# portableSpcPlayer.net
KiCad netlist of a schematic drawn in EAGLE
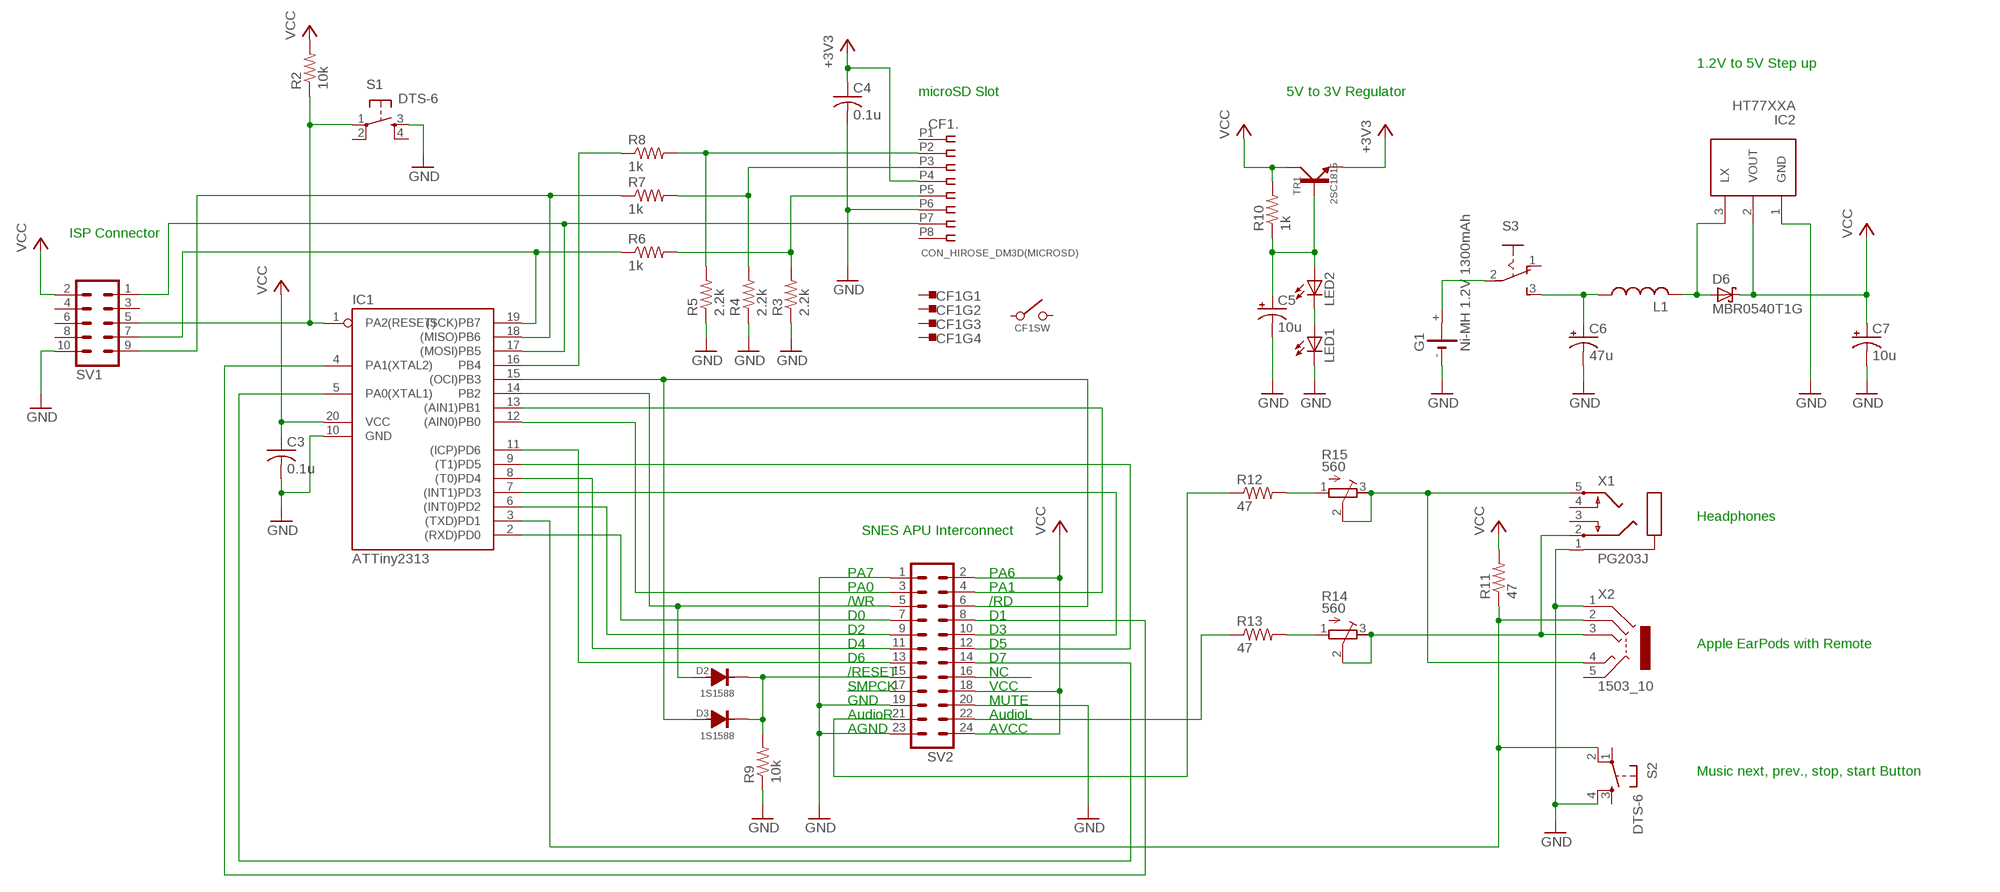
[diagram p0: schematic, sheet 1]

(export (version "E")
  (design (tool "Eeschema 10.0.6"))
  (components
    (comp (ref "C3")
      (value "0.1u")
      (footprint "eagle-import:C050-024X044")
      (libsource (lib "eagle-import") (part "C-US050-024X044"))
    )
    (comp (ref "C4")
      (value "0.1u")
      (footprint "eagle-import:C050-024X044")
      (libsource (lib "eagle-import") (part "C-US050-024X044"))
    )
    (comp (ref "C5")
      (value "10u")
      (footprint "eagle-import:E5-5")
      (libsource (lib "eagle-import") (part "CPOL-USE5-5"))
    )
    (comp (ref "C6")
      (value "47u")
      (footprint "eagle-import:E5-5")
      (libsource (lib "eagle-import") (part "CPOL-USE5-5"))
    )
    (comp (ref "C7")
      (value "10u")
      (footprint "eagle-import:E5-5")
      (libsource (lib "eagle-import") (part "CPOL-USE5-5"))
    )
    (comp (ref "CF1")
      (value "CON_HIROSE_DM3D(MICROSD)")
      (footprint "eagle-import:HIROSE_DM3D(MICRO-SD)")
      (libsource (lib "eagle-import") (part "CON_HIROSE_DM3D(MICROSD)"))
    )
    (comp (ref "D2")
      (value "1S1588")
      (footprint "eagle-import:DIODE-D-5")
      (libsource (lib "eagle-import") (part "1S1588"))
    )
    (comp (ref "D3")
      (value "1S1588")
      (footprint "eagle-import:DIODE-D-5")
      (libsource (lib "eagle-import") (part "1S1588"))
    )
    (comp (ref "D6")
      (value "MBR0540T1G")
      (footprint "eagle-import:DO41-7.6")
      (libsource (lib "eagle-import") (part "1N5817-B"))
    )
    (comp (ref "G1")
      (value "Ni-MH 1.2V 1300mAh")
      (footprint "eagle-import:CRAA")
      (libsource (lib "eagle-import") (part "CR-AA"))
    )
    (comp (ref "IC1")
      (value "ATTiny2313")
      (footprint "eagle-import:DIL20")
      (libsource (lib "eagle-import") (part "AT90S2313P"))
    )
    (comp (ref "IC2")
      (value "HT77XXA")
      (footprint "eagle-import:TO92-N")
      (libsource (lib "eagle-import") (part "HT77XXA"))
    )
    (comp (ref "L1")
      (value "L-US0204/7")
      (footprint "eagle-import:0204_7")
      (libsource (lib "eagle-import") (part "L-US0204/7"))
    )
    (comp (ref "LED1")
      (value "LED3MM")
      (footprint "eagle-import:LED3MM")
      (libsource (lib "eagle-import") (part "LED3MM"))
    )
    (comp (ref "LED2")
      (value "LED3MM")
      (footprint "eagle-import:LED3MM")
      (libsource (lib "eagle-import") (part "LED3MM"))
    )
    (comp (ref "R2")
      (value "10k")
      (footprint "eagle-import:0204_5")
      (libsource (lib "eagle-import") (part "R-US_0204/5"))
    )
    (comp (ref "R3")
      (value "2.2k")
      (footprint "eagle-import:0204_5")
      (libsource (lib "eagle-import") (part "R-US_0204/5"))
    )
    (comp (ref "R4")
      (value "2.2k")
      (footprint "eagle-import:0204_5")
      (libsource (lib "eagle-import") (part "R-US_0204/5"))
    )
    (comp (ref "R5")
      (value "2.2k")
      (footprint "eagle-import:0204_5")
      (libsource (lib "eagle-import") (part "R-US_0204/5"))
    )
    (comp (ref "R6")
      (value "1k")
      (footprint "eagle-import:0204_5")
      (libsource (lib "eagle-import") (part "R-US_0204/5"))
    )
    (comp (ref "R7")
      (value "1k")
      (footprint "eagle-import:0204_5")
      (libsource (lib "eagle-import") (part "R-US_0204/5"))
    )
    (comp (ref "R8")
      (value "1k")
      (footprint "eagle-import:0204_5")
      (libsource (lib "eagle-import") (part "R-US_0204/5"))
    )
    (comp (ref "R9")
      (value "10k")
      (footprint "eagle-import:0204_5")
      (libsource (lib "eagle-import") (part "R-US_0204/5"))
    )
    (comp (ref "R10")
      (value "1k")
      (footprint "eagle-import:0204_5")
      (libsource (lib "eagle-import") (part "R-US_0204/5"))
    )
    (comp (ref "R11")
      (value "47")
      (footprint "eagle-import:0204_5")
      (libsource (lib "eagle-import") (part "R-US_0204/5"))
    )
    (comp (ref "R12")
      (value "47")
      (footprint "eagle-import:0204_5")
      (libsource (lib "eagle-import") (part "R-US_0204/5"))
    )
    (comp (ref "R13")
      (value "47")
      (footprint "eagle-import:0204_5")
      (libsource (lib "eagle-import") (part "R-US_0204/5"))
    )
    (comp (ref "R14")
      (value "560")
      (footprint "eagle-import:RTRIM4G_J")
      (libsource (lib "eagle-import") (part "R-TRIMM4G/J"))
    )
    (comp (ref "R15")
      (value "560")
      (footprint "eagle-import:RTRIM4G_J")
      (libsource (lib "eagle-import") (part "R-TRIMM4G/J"))
    )
    (comp (ref "S1")
      (value "DTS-6")
      (footprint "eagle-import:DTS-6")
      (libsource (lib "eagle-import") (part "DTS-6"))
    )
    (comp (ref "S2")
      (value "DTS-6")
      (footprint "eagle-import:DTS-6")
      (libsource (lib "eagle-import") (part "DTS-6"))
    )
    (comp (ref "S3")
      (value "255SB")
      (footprint "eagle-import:255SB")
      (libsource (lib "eagle-import") (part "255SB"))
    )
    (comp (ref "SV1")
      (value "MA05-2")
      (footprint "eagle-import:MA05-2")
      (libsource (lib "eagle-import") (part "MA05-2"))
    )
    (comp (ref "SV2")
      (value "MA12-2")
      (footprint "eagle-import:MA12-2")
      (libsource (lib "eagle-import") (part "MA12-2"))
    )
    (comp (ref "TR1")
      (value "2SC1815")
      (footprint "eagle-import:TO92-")
      (libsource (lib "eagle-import") (part "2SC1815"))
    )
    (comp (ref "X1")
      (value "PG203J")
      (footprint "eagle-import:PG203J")
      (libsource (lib "eagle-import") (part "PG203J"))
    )
    (comp (ref "X2")
      (value "1503_10")
      (footprint "eagle-import:1503_10")
      (libsource (lib "eagle-import") (part "1503_10"))
    )
  )
  (nets
    (net (code "1") (name "+3V3") (class "Default")
      (node (ref "C4") (pin "1") (pinfunction "1_1") (pintype "passive"))
      (node (ref "CF1") (pin "P4") (pinfunction "4_P4") (pintype "passive"))
      (node (ref "TR1") (pin "3") (pinfunction "3_3") (pintype "passive"))
    )
    (net (code "2") (name "GND") (class "Default")
      (node (ref "C3") (pin "2") (pinfunction "2_2") (pintype "passive"))
      (node (ref "C4") (pin "2") (pinfunction "2_2") (pintype "passive"))
      (node (ref "C5") (pin "-") (pinfunction "-_-") (pintype "passive"))
      (node (ref "C6") (pin "-") (pinfunction "-_-") (pintype "passive"))
      (node (ref "C7") (pin "-") (pinfunction "-_-") (pintype "passive"))
      (node (ref "CF1") (pin "P6") (pinfunction "6_P6") (pintype "passive"))
      (node (ref "G1") (pin "-") (pinfunction "-_-") (pintype "passive"))
      (node (ref "IC1") (pin "10") (pinfunction "GND_10") (pintype "power_in"))
      (node (ref "IC2") (pin "1") (pinfunction "GND_1") (pintype "power_in"))
      (node (ref "LED1") (pin "K") (pinfunction "C_K") (pintype "passive"))
      (node (ref "R3") (pin "1") (pinfunction "1_1") (pintype "passive"))
      (node (ref "R4") (pin "1") (pinfunction "1_1") (pintype "passive"))
      (node (ref "R5") (pin "1") (pinfunction "1_1") (pintype "passive"))
      (node (ref "R9") (pin "1") (pinfunction "1_1") (pintype "passive"))
      (node (ref "S1") (pin "3") (pinfunction "3_3") (pintype "passive"))
      (node (ref "S2") (pin "4") (pinfunction "4_4") (pintype "passive"))
      (node (ref "SV1") (pin "10") (pinfunction "10_10") (pintype "passive"))
      (node (ref "SV2") (pin "1") (pinfunction "1_1") (pintype "passive"))
      (node (ref "SV2") (pin "19") (pinfunction "19_19") (pintype "passive"))
      (node (ref "SV2") (pin "20") (pinfunction "20_20") (pintype "passive"))
      (node (ref "SV2") (pin "23") (pinfunction "23_23") (pintype "passive"))
      (node (ref "X1") (pin "1") (pinfunction "1_1") (pintype "passive"))
      (node (ref "X2") (pin "1") (pinfunction "1_1") (pintype "passive"))
    )
    (net (code "3") (name "Net-(C5-Pad+)") (class "Default")
      (node (ref "C5") (pin "+") (pinfunction "+_+") (pintype "passive"))
      (node (ref "LED2") (pin "A") (pinfunction "A_A") (pintype "passive"))
      (node (ref "R10") (pin "1") (pinfunction "1_1") (pintype "passive"))
      (node (ref "TR1") (pin "1") (pinfunction "1_1") (pintype "passive"))
    )
    (net (code "4") (name "Net-(CF1A-2)") (class "Default")
      (node (ref "CF1") (pin "P2") (pinfunction "2_P2") (pintype "passive"))
      (node (ref "R5") (pin "2") (pinfunction "2_2") (pintype "passive"))
      (node (ref "R8") (pin "2") (pinfunction "2_2") (pintype "passive"))
    )
    (net (code "5") (name "Net-(CF1A-3)") (class "Default")
      (node (ref "CF1") (pin "P3") (pinfunction "3_P3") (pintype "passive"))
      (node (ref "R4") (pin "2") (pinfunction "2_2") (pintype "passive"))
      (node (ref "R7") (pin "2") (pinfunction "2_2") (pintype "passive"))
    )
    (net (code "6") (name "Net-(CF1A-5)") (class "Default")
      (node (ref "CF1") (pin "P5") (pinfunction "5_P5") (pintype "passive"))
      (node (ref "R3") (pin "2") (pinfunction "2_2") (pintype "passive"))
      (node (ref "R6") (pin "2") (pinfunction "2_2") (pintype "passive"))
    )
    (net (code "7") (name "Net-(CF1A-7)") (class "Default")
      (node (ref "CF1") (pin "P7") (pinfunction "7_P7") (pintype "passive"))
      (node (ref "IC1") (pin "17") (pinfunction "(MOSI)PB5_17") (pintype "bidirectional"))
      (node (ref "SV1") (pin "1") (pinfunction "1_1") (pintype "passive"))
    )
    (net (code "8") (name "Net-(D2-PadP$1)") (class "Default")
      (node (ref "D2") (pin "P$1") (pinfunction "P$1_P$1") (pintype "passive"))
      (node (ref "D3") (pin "P$1") (pinfunction "P$1_P$1") (pintype "passive"))
      (node (ref "R9") (pin "2") (pinfunction "2_2") (pintype "passive"))
      (node (ref "SV2") (pin "15") (pinfunction "15_15") (pintype "passive"))
    )
    (net (code "9") (name "Net-(IC1-(AIN0)PB0)") (class "Default")
      (node (ref "IC1") (pin "12") (pinfunction "(AIN0)PB0_12") (pintype "bidirectional"))
      (node (ref "SV2") (pin "3") (pinfunction "3_3") (pintype "passive"))
    )
    (net (code "10") (name "Net-(IC1-(AIN1)PB1)") (class "Default")
      (node (ref "IC1") (pin "13") (pinfunction "(AIN1)PB1_13") (pintype "bidirectional"))
      (node (ref "SV2") (pin "4") (pinfunction "4_4") (pintype "passive"))
    )
    (net (code "11") (name "Net-(IC1-(ICP)PD6)") (class "Default")
      (node (ref "IC1") (pin "11") (pinfunction "(ICP)PD6_11") (pintype "bidirectional"))
      (node (ref "SV2") (pin "13") (pinfunction "13_13") (pintype "passive"))
    )
    (net (code "12") (name "Net-(IC1-(INT0)PD2)") (class "Default")
      (node (ref "IC1") (pin "6") (pinfunction "(INT0)PD2_6") (pintype "bidirectional"))
      (node (ref "SV2") (pin "9") (pinfunction "9_9") (pintype "passive"))
    )
    (net (code "13") (name "Net-(IC1-(INT1)PD3)") (class "Default")
      (node (ref "IC1") (pin "7") (pinfunction "(INT1)PD3_7") (pintype "bidirectional"))
      (node (ref "SV2") (pin "10") (pinfunction "10_10") (pintype "passive"))
    )
    (net (code "14") (name "Net-(IC1-(MISO)PB6)") (class "Default")
      (node (ref "IC1") (pin "18") (pinfunction "(MISO)PB6_18") (pintype "bidirectional"))
      (node (ref "R7") (pin "1") (pinfunction "1_1") (pintype "passive"))
      (node (ref "SV1") (pin "9") (pinfunction "9_9") (pintype "passive"))
    )
    (net (code "15") (name "Net-(IC1-(OCI)PB3)") (class "Default")
      (node (ref "D3") (pin "P$2") (pinfunction "P$2_P$2") (pintype "passive"))
      (node (ref "IC1") (pin "15") (pinfunction "(OCI)PB3_15") (pintype "bidirectional"))
      (node (ref "SV2") (pin "6") (pinfunction "6_6") (pintype "passive"))
    )
    (net (code "16") (name "Net-(IC1-(RXD)PD0)") (class "Default")
      (node (ref "IC1") (pin "2") (pinfunction "(RXD)PD0_2") (pintype "bidirectional"))
      (node (ref "SV2") (pin "7") (pinfunction "7_7") (pintype "passive"))
    )
    (net (code "17") (name "Net-(IC1-(SCK)PB7)") (class "Default")
      (node (ref "IC1") (pin "19") (pinfunction "(SCK)PB7_19") (pintype "bidirectional"))
      (node (ref "R6") (pin "1") (pinfunction "1_1") (pintype "passive"))
      (node (ref "SV1") (pin "7") (pinfunction "7_7") (pintype "passive"))
    )
    (net (code "18") (name "Net-(IC1-(T0)PD4)") (class "Default")
      (node (ref "IC1") (pin "8") (pinfunction "(T0)PD4_8") (pintype "bidirectional"))
      (node (ref "SV2") (pin "11") (pinfunction "11_11") (pintype "passive"))
    )
    (net (code "19") (name "Net-(IC1-(T1)PD5)") (class "Default")
      (node (ref "IC1") (pin "9") (pinfunction "(T1)PD5_9") (pintype "bidirectional"))
      (node (ref "SV2") (pin "12") (pinfunction "12_12") (pintype "passive"))
    )
    (net (code "20") (name "Net-(IC1-(TXD)PD1)") (class "Default")
      (node (ref "IC1") (pin "3") (pinfunction "(TXD)PD1_3") (pintype "bidirectional"))
      (node (ref "R11") (pin "1") (pinfunction "1_1") (pintype "passive"))
      (node (ref "S2") (pin "2") (pinfunction "2_2") (pintype "passive"))
      (node (ref "X2") (pin "2") (pinfunction "2_2") (pintype "passive"))
    )
    (net (code "21") (name "Net-(IC1-PA0(XTAL1))") (class "Default")
      (node (ref "IC1") (pin "5") (pinfunction "PA0(XTAL1)_5") (pintype "bidirectional"))
      (node (ref "SV2") (pin "14") (pinfunction "14_14") (pintype "passive"))
    )
    (net (code "22") (name "Net-(IC1-PA1(XTAL2))") (class "Default")
      (node (ref "IC1") (pin "4") (pinfunction "PA1(XTAL2)_4") (pintype "bidirectional"))
      (node (ref "SV2") (pin "8") (pinfunction "8_8") (pintype "passive"))
    )
    (net (code "23") (name "Net-(IC1-PA2(RESET))") (class "Default")
      (node (ref "IC1") (pin "1") (pinfunction "PA2(RESET)_1") (pintype "bidirectional"))
      (node (ref "R2") (pin "1") (pinfunction "1_1") (pintype "passive"))
      (node (ref "S1") (pin "1") (pinfunction "1_1") (pintype "passive"))
      (node (ref "SV1") (pin "5") (pinfunction "5_5") (pintype "passive"))
    )
    (net (code "24") (name "Net-(IC1-PB2)") (class "Default")
      (node (ref "D2") (pin "P$2") (pinfunction "P$2_P$2") (pintype "passive"))
      (node (ref "IC1") (pin "14") (pinfunction "PB2_14") (pintype "bidirectional"))
      (node (ref "SV2") (pin "5") (pinfunction "5_5") (pintype "passive"))
    )
    (net (code "25") (name "Net-(IC1-PB4)") (class "Default")
      (node (ref "IC1") (pin "16") (pinfunction "PB4_16") (pintype "bidirectional"))
      (node (ref "R8") (pin "1") (pinfunction "1_1") (pintype "passive"))
    )
    (net (code "26") (name "Net-(IC2-LX)") (class "Default")
      (node (ref "D6") (pin "A") (pinfunction "A_A") (pintype "passive"))
      (node (ref "IC2") (pin "3") (pinfunction "LX_3") (pintype "input"))
      (node (ref "L1") (pin "2") (pinfunction "2_2") (pintype "passive"))
    )
    (net (code "27") (name "Net-(LED2-C)") (class "Default")
      (node (ref "LED1") (pin "A") (pinfunction "A_A") (pintype "passive"))
      (node (ref "LED2") (pin "K") (pinfunction "C_K") (pintype "passive"))
    )
    (net (code "28") (name "Net-(R12-Pad1)") (class "Default")
      (node (ref "R12") (pin "1") (pinfunction "1_1") (pintype "passive"))
      (node (ref "SV2") (pin "21") (pinfunction "21_21") (pintype "passive"))
    )
    (net (code "29") (name "Net-(R13-Pad1)") (class "Default")
      (node (ref "R13") (pin "1") (pinfunction "1_1") (pintype "passive"))
      (node (ref "SV2") (pin "22") (pinfunction "22_22") (pintype "passive"))
    )
    (net (code "30") (name "Net-(R14-A)") (class "Default")
      (node (ref "R13") (pin "2") (pinfunction "2_2") (pintype "passive"))
      (node (ref "R14") (pin "1") (pinfunction "A_1") (pintype "passive"))
    )
    (net (code "31") (name "Net-(R14-E)") (class "Default")
      (node (ref "R14") (pin "2") (pinfunction "S_2") (pintype "passive"))
      (node (ref "R14") (pin "3") (pinfunction "E_3") (pintype "passive"))
      (node (ref "X1") (pin "2") (pinfunction "2_2") (pintype "passive"))
      (node (ref "X2") (pin "3") (pinfunction "3_3") (pintype "passive"))
    )
    (net (code "32") (name "Net-(R15-A)") (class "Default")
      (node (ref "R12") (pin "2") (pinfunction "2_2") (pintype "passive"))
      (node (ref "R15") (pin "1") (pinfunction "A_1") (pintype "passive"))
    )
    (net (code "33") (name "Net-(R15-E)") (class "Default")
      (node (ref "R15") (pin "2") (pinfunction "S_2") (pintype "passive"))
      (node (ref "R15") (pin "3") (pinfunction "E_3") (pintype "passive"))
      (node (ref "X1") (pin "5") (pinfunction "5_5") (pintype "passive"))
      (node (ref "X2") (pin "4") (pinfunction "4_4") (pintype "passive"))
    )
    (net (code "34") (name "Net-(S3-P)") (class "Default")
      (node (ref "G1") (pin "+") (pinfunction "+_+") (pintype "passive"))
      (node (ref "S3") (pin "2") (pinfunction "P_2") (pintype "passive"))
    )
    (net (code "35") (name "Net-(S3-S)") (class "Default")
      (node (ref "C6") (pin "+") (pinfunction "+_+") (pintype "passive"))
      (node (ref "L1") (pin "1") (pinfunction "1_1") (pintype "passive"))
      (node (ref "S3") (pin "3") (pinfunction "S_3") (pintype "passive"))
    )
    (net (code "36") (name "VCC") (class "Default")
      (node (ref "C3") (pin "1") (pinfunction "1_1") (pintype "passive"))
      (node (ref "C7") (pin "+") (pinfunction "+_+") (pintype "passive"))
      (node (ref "D6") (pin "C") (pinfunction "C_C") (pintype "passive"))
      (node (ref "IC1") (pin "20") (pinfunction "VCC_20") (pintype "power_in"))
      (node (ref "IC2") (pin "2") (pinfunction "VOUT_2") (pintype "power_in"))
      (node (ref "R10") (pin "2") (pinfunction "2_2") (pintype "passive"))
      (node (ref "R11") (pin "2") (pinfunction "2_2") (pintype "passive"))
      (node (ref "R2") (pin "2") (pinfunction "2_2") (pintype "passive"))
      (node (ref "SV1") (pin "2") (pinfunction "2_2") (pintype "passive"))
      (node (ref "SV2") (pin "18") (pinfunction "18_18") (pintype "passive"))
      (node (ref "SV2") (pin "2") (pinfunction "2_2") (pintype "passive"))
      (node (ref "SV2") (pin "24") (pinfunction "24_24") (pintype "passive"))
      (node (ref "TR1") (pin "2") (pinfunction "2_2") (pintype "passive"))
    )
    (net (code "37") (name "unconnected-(CF1A-1-PadP1)") (class "Default")
      (node (ref "CF1") (pin "P1") (pinfunction "1_P1") (pintype "passive"))
    )
    (net (code "38") (name "unconnected-(CF1A-8-PadP8)") (class "Default")
      (node (ref "CF1") (pin "P8") (pinfunction "8_P8") (pintype "passive"))
    )
    (net (code "39") (name "unconnected-(CF1B-PAD-PadG1)") (class "Default")
      (node (ref "CF1") (pin "G1") (pinfunction "PAD_G1") (pintype "passive"))
    )
    (net (code "40") (name "unconnected-(CF1C-PAD-PadG2)") (class "Default")
      (node (ref "CF1") (pin "G2") (pinfunction "PAD_G2") (pintype "passive"))
    )
    (net (code "41") (name "unconnected-(CF1D-PAD-PadG3)") (class "Default")
      (node (ref "CF1") (pin "G3") (pinfunction "PAD_G3") (pintype "passive"))
    )
    (net (code "42") (name "unconnected-(CF1E-PAD-PadG4)") (class "Default")
      (node (ref "CF1") (pin "G4") (pinfunction "PAD_G4") (pintype "passive"))
    )
    (net (code "43") (name "unconnected-(CF1F-0-PadS0)") (class "Default")
      (node (ref "CF1") (pin "S0") (pinfunction "0_S0") (pintype "passive"))
    )
    (net (code "44") (name "unconnected-(CF1F-1-PadS1)") (class "Default")
      (node (ref "CF1") (pin "S1") (pinfunction "1_S1") (pintype "passive"))
    )
    (net (code "45") (name "unconnected-(G1-+-Pad+@1)") (class "Default")
      (node (ref "G1") (pin "+@1") (pinfunction "+_+@1") (pintype "passive"))
    )
    (net (code "46") (name "unconnected-(S1-Pad2)") (class "Default")
      (node (ref "S1") (pin "2") (pinfunction "2_2") (pintype "passive"))
    )
    (net (code "47") (name "unconnected-(S1-Pad4)") (class "Default")
      (node (ref "S1") (pin "4") (pinfunction "4_4") (pintype "passive"))
    )
    (net (code "48") (name "unconnected-(S2-Pad1)") (class "Default")
      (node (ref "S2") (pin "1") (pinfunction "1_1") (pintype "passive"))
    )
    (net (code "49") (name "unconnected-(S2-Pad3)") (class "Default")
      (node (ref "S2") (pin "3") (pinfunction "3_3") (pintype "passive"))
    )
    (net (code "50") (name "unconnected-(S3-O-Pad1)") (class "Default")
      (node (ref "S3") (pin "1") (pinfunction "O_1") (pintype "passive"))
    )
    (net (code "51") (name "unconnected-(SV1-Pad3)") (class "Default")
      (node (ref "SV1") (pin "3") (pinfunction "3_3") (pintype "passive"))
    )
    (net (code "52") (name "unconnected-(SV1-Pad4)") (class "Default")
      (node (ref "SV1") (pin "4") (pinfunction "4_4") (pintype "passive"))
    )
    (net (code "53") (name "unconnected-(SV1-Pad6)") (class "Default")
      (node (ref "SV1") (pin "6") (pinfunction "6_6") (pintype "passive"))
    )
    (net (code "54") (name "unconnected-(SV1-Pad8)") (class "Default")
      (node (ref "SV1") (pin "8") (pinfunction "8_8") (pintype "passive"))
    )
    (net (code "55") (name "unconnected-(SV2-Pad16)") (class "Default")
      (node (ref "SV2") (pin "16") (pinfunction "16_16") (pintype "passive"))
    )
    (net (code "56") (name "unconnected-(SV2-Pad17)") (class "Default")
      (node (ref "SV2") (pin "17") (pinfunction "17_17") (pintype "passive"))
    )
    (net (code "57") (name "unconnected-(X1-Pad3)") (class "Default")
      (node (ref "X1") (pin "3") (pinfunction "3_3") (pintype "passive"))
    )
    (net (code "58") (name "unconnected-(X1-Pad4)") (class "Default")
      (node (ref "X1") (pin "4") (pinfunction "4_4") (pintype "passive"))
    )
    (net (code "59") (name "unconnected-(X2-Pad5)") (class "Default")
      (node (ref "X2") (pin "5") (pinfunction "5_5") (pintype "passive"))
    )
  )
)
